# High_Voltage_Converter.net
KiCad netlist of a schematic drawn in Altium Designer
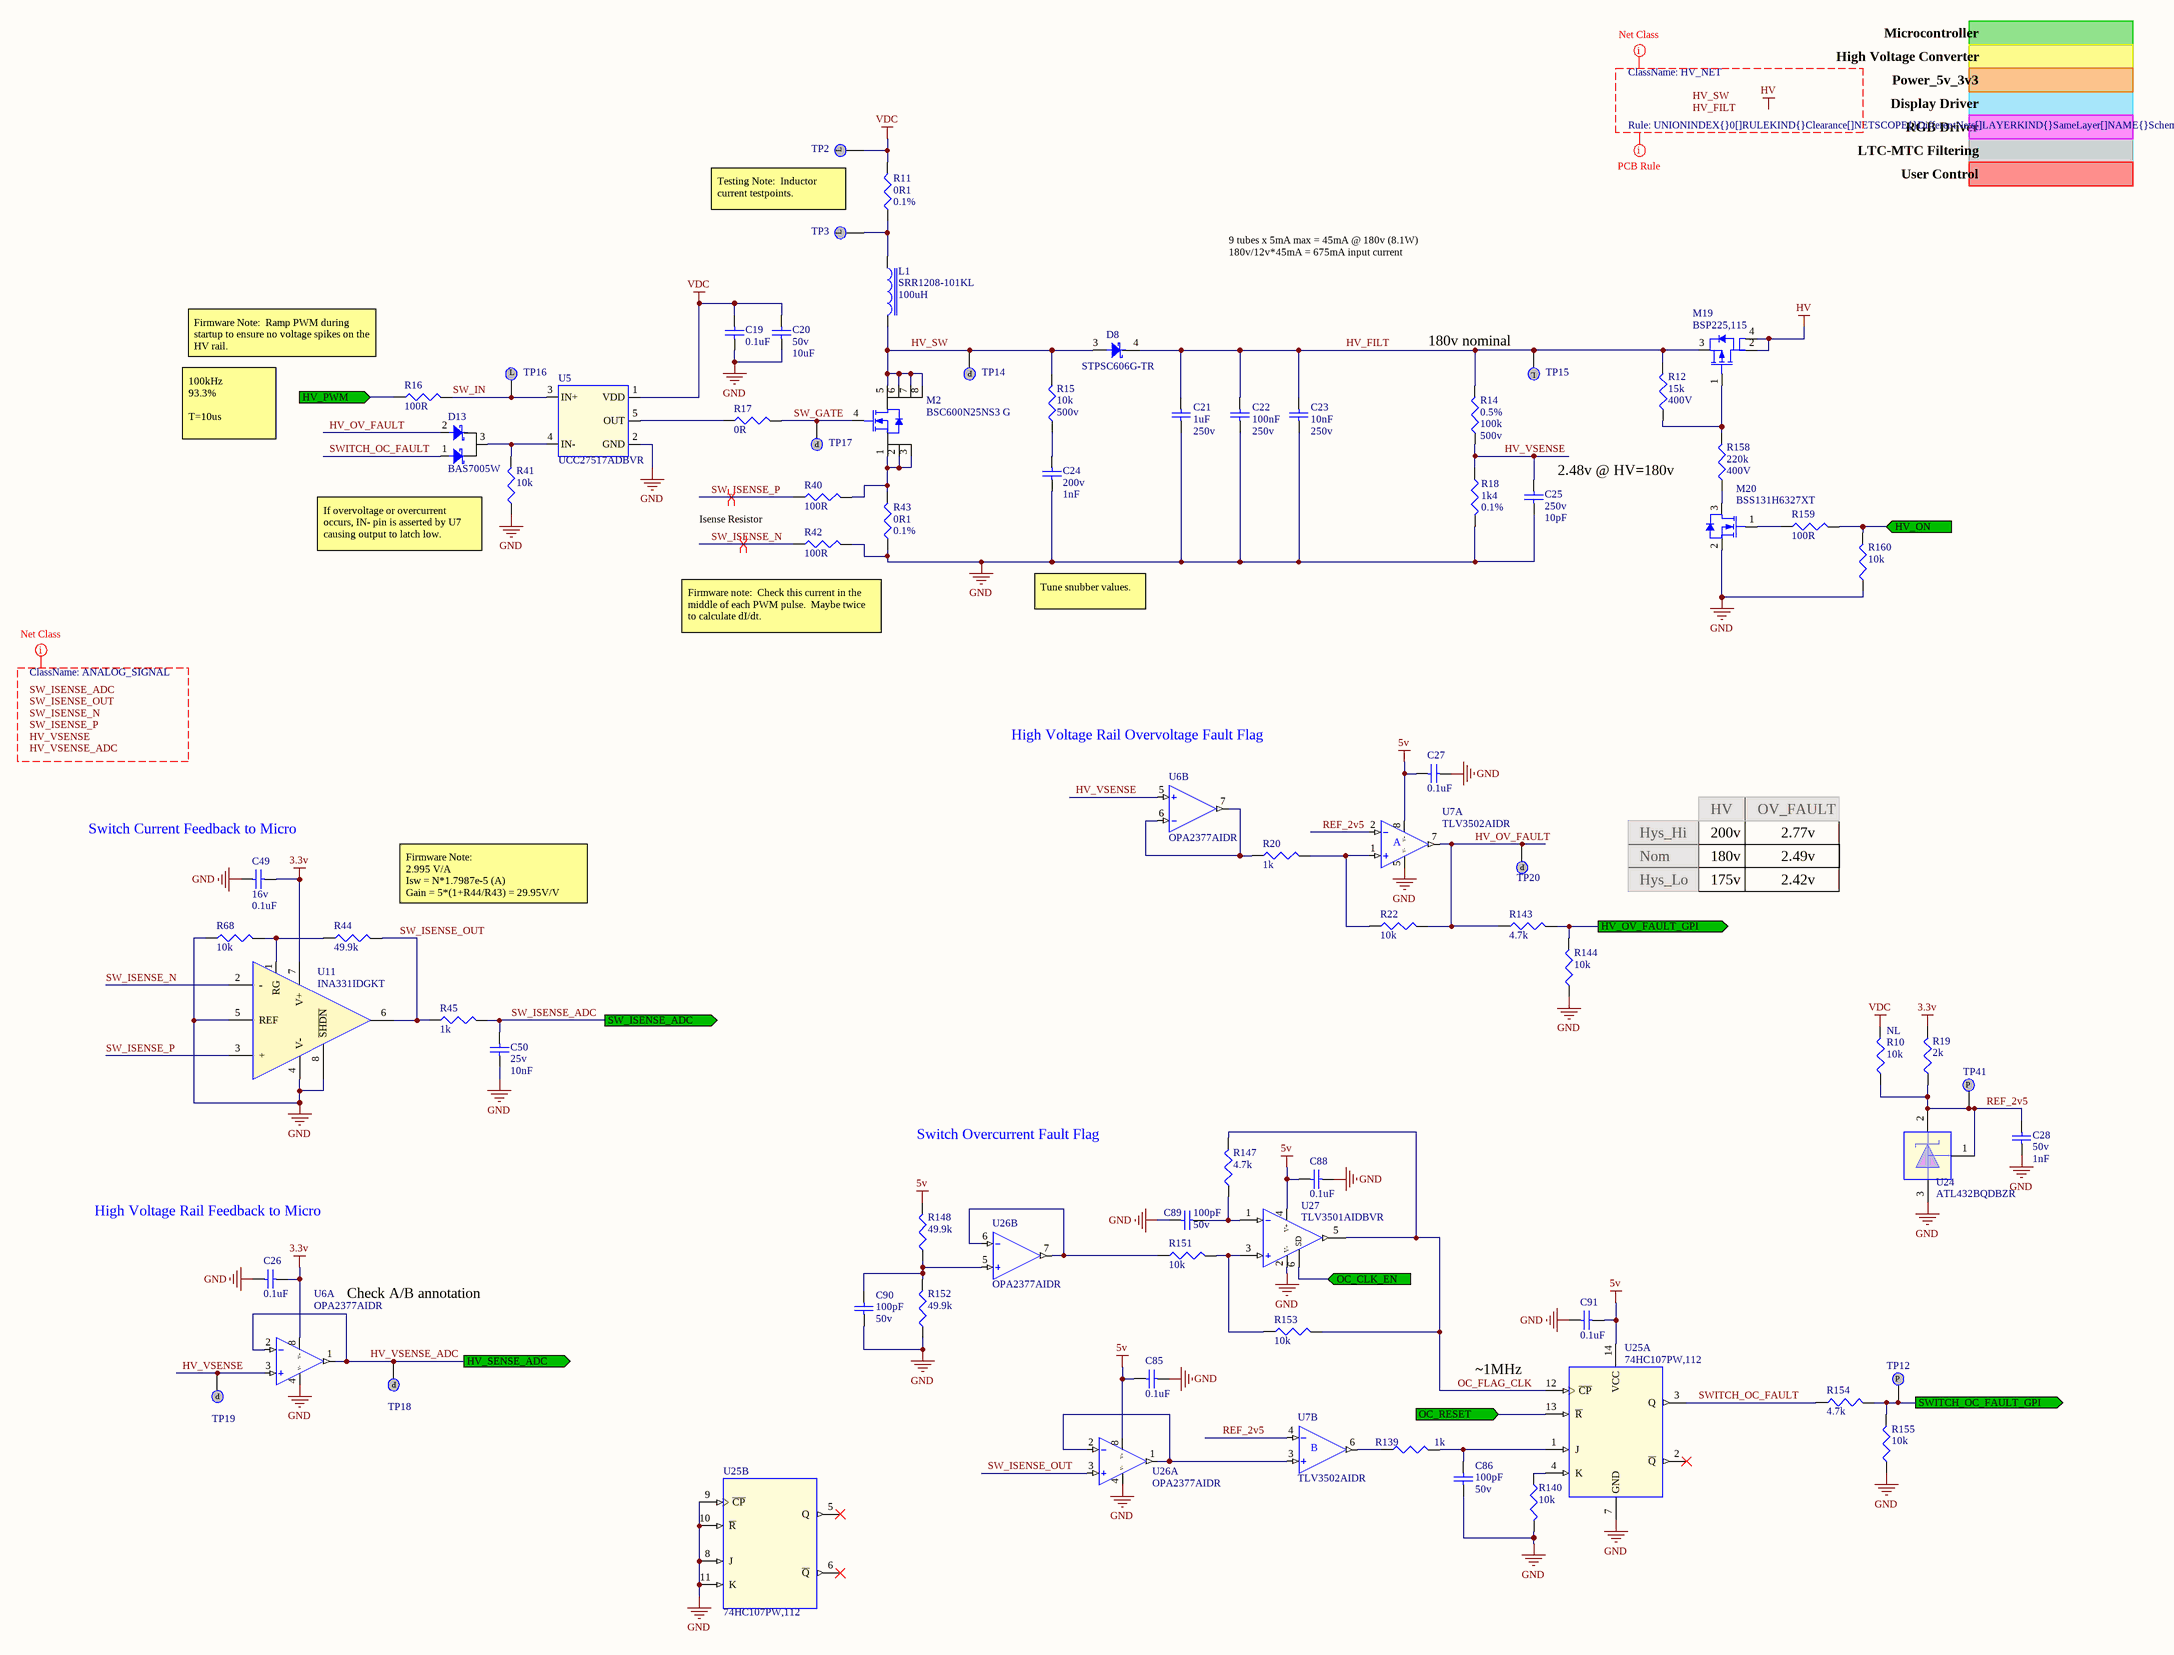
[diagram p0: High Voltage Converter.SchDoc]

(export (version "E")
  (design (tool "Eeschema 10.0.6"))
  (components
    (comp (ref "C19")
      (value "0.1uF")
      (footprint "CAP0603R")
      (fields (field (name "MFG") "Vishay") (field (name "VOLTAGE") "50v"))
      (libsource (lib "Altium Library") (part "0.1uF 50v (0603)"))
    )
    (comp (ref "C20")
      (value "10uF")
      (footprint "CAP1206R")
      (fields (field (name "TOLERANCE") "10%") (field (name "MFG") "TDK") (field (name "VOLTAGE") "50v"))
      (libsource (lib "Altium Library") (part "10uF 50v (1206)"))
    )
    (comp (ref "C21")
      (value "1uF")
      (footprint "CAP2220R")
      (fields (field (name "TOLERANCE") "10%") (field (name "MFG") "Murata") (field (name "VOLTAGE") "250v"))
      (libsource (lib "Altium Library") (part "1uF 250v (2220)"))
    )
    (comp (ref "C22")
      (value "100nF")
      (footprint "CAP1206R")
      (fields (field (name "TOLERANCE") "10%") (field (name "MFG") "Murata") (field (name "VOLTAGE") "250v"))
      (libsource (lib "Altium Library") (part "100nF 250v (1206)"))
    )
    (comp (ref "C23")
      (value "10nF")
      (footprint "CAP0805R")
      (fields (field (name "TOLERANCE") "10%") (field (name "MFG") "Murata") (field (name "VOLTAGE") "250v"))
      (libsource (lib "Altium Library") (part "10nF 250v (0805)"))
    )
    (comp (ref "C24")
      (value "1nF")
      (footprint "CAP0805R")
      (fields (field (name "MFG") "Vishay") (field (name "VOLTAGE") "200v"))
      (libsource (lib "Altium Library") (part "1nF 200v (0805)"))
    )
    (comp (ref "C25")
      (value "10pF")
      (footprint "CAP0805R")
      (fields (field (name "TOLERANCE") "5%") (field (name "MFG") "Murata") (field (name "VOLTAGE") "250v"))
      (libsource (lib "Altium Library") (part "10pF 250V (0805)"))
    )
    (comp (ref "C26")
      (value "0.1uF")
      (footprint "CAP0402R")
      (fields (field (name "TOLERANCE") "20%") (field (name "MFG") "Vishay") (field (name "VOLTAGE") "10v"))
      (libsource (lib "Altium Library") (part "0.1uF 10v (0402)"))
    )
    (comp (ref "C27")
      (value "0.1uF")
      (footprint "CAP0402R")
      (fields (field (name "TOLERANCE") "20%") (field (name "MFG") "Vishay") (field (name "VOLTAGE") "10v"))
      (libsource (lib "Altium Library") (part "0.1uF 10v (0402)"))
    )
    (comp (ref "C28")
      (value "1nF")
      (footprint "CAP0402R")
      (fields (field (name "TOLERANCE") "10%") (field (name "MFG") "Vishay") (field (name "VOLTAGE") "50v"))
      (libsource (lib "Altium Library") (part "1nF 50v (0402)"))
    )
    (comp (ref "C49")
      (value "0.1uF")
      (footprint "CAP0603R")
      (fields (field (name "MFG") "Vishay") (field (name "VOLTAGE") "16v"))
      (libsource (lib "Altium Library") (part "0.1uF 16v (0603)"))
    )
    (comp (ref "C50")
      (value "10nF")
      (footprint "CAP0402R")
      (fields (field (name "TOLERANCE") "5%") (field (name "MFG") "Vishay") (field (name "VOLTAGE") "25v"))
      (libsource (lib "Altium Library") (part "10nF 25v (0402)"))
    )
    (comp (ref "C85")
      (value "0.1uF")
      (footprint "CAP0402R")
      (fields (field (name "TOLERANCE") "20%") (field (name "MFG") "Vishay") (field (name "VOLTAGE") "10v"))
      (libsource (lib "Altium Library") (part "0.1uF 10v (0402)"))
    )
    (comp (ref "C86")
      (value "100pF")
      (footprint "CAP0402R")
      (fields (field (name "TOLERANCE") "10%") (field (name "MFG") "MURATA") (field (name "VOLTAGE") "50v"))
      (libsource (lib "Altium Library") (part "100pF 50v (0402)"))
    )
    (comp (ref "C88")
      (value "0.1uF")
      (footprint "CAP0402R")
      (fields (field (name "TOLERANCE") "20%") (field (name "MFG") "Vishay") (field (name "VOLTAGE") "10v"))
      (libsource (lib "Altium Library") (part "0.1uF 10v (0402)"))
    )
    (comp (ref "C89")
      (value "100pF")
      (footprint "CAP0402R")
      (fields (field (name "TOLERANCE") "10%") (field (name "MFG") "MURATA") (field (name "VOLTAGE") "50v"))
      (libsource (lib "Altium Library") (part "100pF 50v (0402)"))
    )
    (comp (ref "C90")
      (value "100pF")
      (footprint "CAP0402R")
      (fields (field (name "TOLERANCE") "10%") (field (name "MFG") "MURATA") (field (name "VOLTAGE") "50v"))
      (libsource (lib "Altium Library") (part "100pF 50v (0402)"))
    )
    (comp (ref "C91")
      (value "0.1uF")
      (footprint "CAP0402R")
      (fields (field (name "TOLERANCE") "20%") (field (name "MFG") "Vishay") (field (name "VOLTAGE") "10v"))
      (libsource (lib "Altium Library") (part "0.1uF 10v (0402)"))
    )
    (comp (ref "D8")
      (value "STPSC606G-TR")
      (footprint "D2PAK-3")
      (description "Schottky, 6A, 600v")
      (fields (field (name "MFG") "STMICRO"))
      (libsource (lib "Altium Library") (part "STPSC606G-TR"))
    )
    (comp (ref "D13")
      (value "BAS7005W")
      (footprint "SOT-323")
      (description "Schottky, Dual, Common Cathode")
      (fields (field (name "MFG") "Vishay"))
      (libsource (lib "Altium Library") (part "BAS7005WH6327XTSA1"))
    )
    (comp (ref "L1")
      (value "100uH")
      (footprint "SRR1208")
      (fields (field (name "MFG") "Bourns") (field (name "MFG_PN") "SRR1208-101KL"))
      (libsource (lib "Altium Library") (part "100uH_SRR1208"))
    )
    (comp (ref "M2")
      (value "BSC600N25NS3 G")
      (footprint "PowerPAK-SO8")
      (description "NFET_SINGLE_25A_250V")
      (fields (field (name "MFG") "Infineon") (field (name "MFG_PN") "BSC600N25NS3 G"))
      (libsource (lib "Altium Library") (part "BSC600N25NS3 G"))
    )
    (comp (ref "M19")
      (value "BSP225,115")
      (footprint "SOT223")
      (description "PFET_SINGLE_0.225A_1.5W_250V")
      (fields (field (name "MFG") "NXP"))
      (libsource (lib "Altium Library") (part "BSP225,115"))
    )
    (comp (ref "M20")
      (value "BSS131H6327XT")
      (footprint "SOT23-3 REFLOW")
      (description "NFET_SINGLE_100mA_240v")
      (fields (field (name "MFG") "INFINEON"))
      (libsource (lib "Altium Library") (part "BSS131H6327XT"))
    )
    (comp (ref "R10")
      (value "10k")
      (footprint "RES0402R")
      (fields
        (field (name "TOLERANCE") "1%")
        (field (name "POWER") "63mW")
        (field (name "MFG") "Vishay")
        (field (name "LOAD") "NL")
      )
      (libsource (lib "Altium Library") (part "10k (0402)"))
    )
    (comp (ref "R11")
      (value "0R1")
      (footprint "RES1206R")
      (fields (field (name "POWER") "1W") (field (name "MFG") "Vishay") (field (name "TOLERANCE") "0.1%"))
      (libsource (lib "Altium Library") (part "100m 0.1% (1206)"))
    )
    (comp (ref "R12")
      (value "15k")
      (footprint "RES2010R")
      (fields
        (field (name "TOLERANCE") "1%")
        (field (name "POWER") "0.750mW")
        (field (name "MFG") "VISHAY")
        (field (name "VOLTAGE") "400V")
      )
      (libsource (lib "Altium Library") (part "15k 400v (2010)"))
    )
    (comp (ref "R14")
      (value "100k")
      (footprint "RES1206R")
      (fields
        (field (name "POWER") "0.25mW")
        (field (name "MFG") "KOA SPEER")
        (field (name "TOLERANCE") "0.5%")
        (field (name "VOLTAGE") "500v")
      )
      (libsource (lib "Altium Library") (part "100k 500v (1206)"))
    )
    (comp (ref "R15")
      (value "10k")
      (footprint "RES1206R")
      (fields
        (field (name "TOLERANCE") "5%")
        (field (name "POWER") "0.66mW")
        (field (name "MFG") "Panasonic")
        (field (name "VOLTAGE") "500v")
      )
      (libsource (lib "Altium Library") (part "10k 500v (1206)"))
    )
    (comp (ref "R16")
      (value "100R")
      (footprint "RES0402R")
      (fields (field (name "TOLERANCE") "1%") (field (name "POWER") "63mW") (field (name "MFG") "Vishay"))
      (libsource (lib "Altium Library") (part "100R (0402)"))
    )
    (comp (ref "R17")
      (value "0R")
      (footprint "RES0603R")
      (fields (field (name "MFG") "Vishay"))
      (libsource (lib "Altium Library") (part "0R (0603)"))
    )
    (comp (ref "R18")
      (value "1k4")
      (footprint "RES0603R")
      (fields (field (name "TOLERANCE") "0.1%") (field (name "POWER") "0.1W"))
      (libsource (lib "Altium Library") (part "1k4   0.1%"))
    )
    (comp (ref "R19")
      (value "2k")
      (footprint "RES0402R")
      (fields (field (name "TOLERANCE") "1%") (field (name "POWER") "63mW") (field (name "MFG") "Vishay"))
      (libsource (lib "Altium Library") (part "2k (0402)"))
    )
    (comp (ref "R20")
      (value "1k")
      (footprint "RES0402R")
      (fields (field (name "TOLERANCE") "1%") (field (name "POWER") "63mW") (field (name "MFG") "Vishay"))
      (libsource (lib "Altium Library") (part "1k (0402)"))
    )
    (comp (ref "R22")
      (value "10k")
      (footprint "RES0402R")
      (fields (field (name "TOLERANCE") "1%") (field (name "POWER") "63mW") (field (name "MFG") "Vishay"))
      (libsource (lib "Altium Library") (part "10k (0402)"))
    )
    (comp (ref "R40")
      (value "100R")
      (footprint "RES0402R")
      (fields (field (name "TOLERANCE") "1%") (field (name "POWER") "63mW") (field (name "MFG") "Vishay"))
      (libsource (lib "Altium Library") (part "100R (0402)"))
    )
    (comp (ref "R41")
      (value "10k")
      (footprint "RES0402R")
      (fields (field (name "TOLERANCE") "1%") (field (name "POWER") "63mW") (field (name "MFG") "Vishay"))
      (libsource (lib "Altium Library") (part "10k (0402)"))
    )
    (comp (ref "R42")
      (value "100R")
      (footprint "RES0402R")
      (fields (field (name "TOLERANCE") "1%") (field (name "POWER") "63mW") (field (name "MFG") "Vishay"))
      (libsource (lib "Altium Library") (part "100R (0402)"))
    )
    (comp (ref "R43")
      (value "0R1")
      (footprint "RES1206R")
      (fields (field (name "POWER") "1W") (field (name "MFG") "Vishay") (field (name "TOLERANCE") "0.1%"))
      (libsource (lib "Altium Library") (part "100m 0.1% (1206)"))
    )
    (comp (ref "R44")
      (value "49.9k")
      (footprint "RES0402R")
      (fields (field (name "TOLERANCE") "1%") (field (name "POWER") "63mW") (field (name "MFG") "Vishay"))
      (libsource (lib "Altium Library") (part "49.9k (0402)"))
    )
    (comp (ref "R45")
      (value "1k")
      (footprint "RES0402R")
      (fields (field (name "TOLERANCE") "1%") (field (name "POWER") "63mW") (field (name "MFG") "Vishay"))
      (libsource (lib "Altium Library") (part "1k (0402)"))
    )
    (comp (ref "R68")
      (value "10k")
      (footprint "RES0402R")
      (fields (field (name "TOLERANCE") "1%") (field (name "POWER") "63mW") (field (name "MFG") "Vishay"))
      (libsource (lib "Altium Library") (part "10k (0402)"))
    )
    (comp (ref "R139")
      (value "1k")
      (footprint "RES0402R")
      (fields (field (name "TOLERANCE") "1%") (field (name "POWER") "63mW") (field (name "MFG") "Vishay"))
      (libsource (lib "Altium Library") (part "1k (0402)"))
    )
    (comp (ref "R140")
      (value "10k")
      (footprint "RES0402R")
      (fields (field (name "TOLERANCE") "1%") (field (name "POWER") "63mW") (field (name "MFG") "Vishay"))
      (libsource (lib "Altium Library") (part "10k (0402)"))
    )
    (comp (ref "R143")
      (value "4.7k")
      (footprint "RES0402R")
      (fields (field (name "TOLERANCE") "1%") (field (name "POWER") "63mW") (field (name "MFG") "Vishay"))
      (libsource (lib "Altium Library") (part "4.7k (0402)"))
    )
    (comp (ref "R144")
      (value "10k")
      (footprint "RES0402R")
      (fields (field (name "TOLERANCE") "1%") (field (name "POWER") "63mW") (field (name "MFG") "Vishay"))
      (libsource (lib "Altium Library") (part "10k (0402)"))
    )
    (comp (ref "R147")
      (value "4.7k")
      (footprint "RES0402R")
      (fields (field (name "TOLERANCE") "1%") (field (name "POWER") "63mW") (field (name "MFG") "Vishay"))
      (libsource (lib "Altium Library") (part "4.7k (0402)"))
    )
    (comp (ref "R148")
      (value "49.9k")
      (footprint "RES0402R")
      (fields (field (name "TOLERANCE") "1%") (field (name "POWER") "63mW") (field (name "MFG") "Vishay"))
      (libsource (lib "Altium Library") (part "49.9k (0402)"))
    )
    (comp (ref "R151")
      (value "10k")
      (footprint "RES0402R")
      (fields (field (name "TOLERANCE") "1%") (field (name "POWER") "63mW") (field (name "MFG") "Vishay"))
      (libsource (lib "Altium Library") (part "10k (0402)"))
    )
    (comp (ref "R152")
      (value "49.9k")
      (footprint "RES0402R")
      (fields (field (name "TOLERANCE") "1%") (field (name "POWER") "63mW") (field (name "MFG") "Vishay"))
      (libsource (lib "Altium Library") (part "49.9k (0402)"))
    )
    (comp (ref "R153")
      (value "10k")
      (footprint "RES0402R")
      (fields (field (name "TOLERANCE") "1%") (field (name "POWER") "63mW") (field (name "MFG") "Vishay"))
      (libsource (lib "Altium Library") (part "10k (0402)"))
    )
    (comp (ref "R154")
      (value "4.7k")
      (footprint "RES0402R")
      (fields (field (name "TOLERANCE") "1%") (field (name "POWER") "63mW") (field (name "MFG") "Vishay"))
      (libsource (lib "Altium Library") (part "4.7k (0402)"))
    )
    (comp (ref "R155")
      (value "10k")
      (footprint "RES0402R")
      (fields (field (name "TOLERANCE") "1%") (field (name "POWER") "63mW") (field (name "MFG") "Vishay"))
      (libsource (lib "Altium Library") (part "10k (0402)"))
    )
    (comp (ref "R158")
      (value "220k")
      (footprint "RES2010R")
      (fields
        (field (name "TOLERANCE") "1%")
        (field (name "POWER") "0.750mW")
        (field (name "MFG") "VISHAY")
        (field (name "VOLTAGE") "400V")
      )
      (libsource (lib "Altium Library") (part "220k 400v (2010)"))
    )
    (comp (ref "R159")
      (value "100R")
      (footprint "RES0402R")
      (fields (field (name "TOLERANCE") "1%") (field (name "POWER") "63mW") (field (name "MFG") "Vishay"))
      (libsource (lib "Altium Library") (part "100R (0402)"))
    )
    (comp (ref "R160")
      (value "10k")
      (footprint "RES0402R")
      (fields (field (name "TOLERANCE") "1%") (field (name "POWER") "63mW") (field (name "MFG") "Vishay"))
      (libsource (lib "Altium Library") (part "10k (0402)"))
    )
    (comp (ref "TP2")
      (value "5001")
      (footprint "5001 Testpoint")
      (fields (field (name "MFG") "KEYSTONE"))
      (libsource (lib "Altium Library") (part "Testpoint Loop"))
    )
    (comp (ref "TP3")
      (value "5001")
      (footprint "5001 Testpoint")
      (fields (field (name "MFG") "KEYSTONE"))
      (libsource (lib "Altium Library") (part "Testpoint Loop"))
    )
    (comp (ref "TP12")
      (value "NONE")
      (footprint "TESTPOINT - 1.5mm Round Pad")
      (description "1.5mm Testpoint")
      (libsource (lib "Altium Library") (part "Testpoint 1.5mm Pad"))
    )
    (comp (ref "TP14")
      (value "NONE")
      (footprint "TESTPOINT - 1.5mm Round Pad")
      (description "1.5mm Testpoint")
      (libsource (lib "Altium Library") (part "Testpoint 1.5mm Pad"))
    )
    (comp (ref "TP15")
      (value "5001")
      (footprint "5001 Testpoint")
      (fields (field (name "MFG") "KEYSTONE"))
      (libsource (lib "Altium Library") (part "Testpoint Loop"))
    )
    (comp (ref "TP16")
      (value "5001")
      (footprint "5001 Testpoint")
      (fields (field (name "MFG") "KEYSTONE"))
      (libsource (lib "Altium Library") (part "Testpoint Loop"))
    )
    (comp (ref "TP17")
      (value "NONE")
      (footprint "TESTPOINT - 1.5mm Round Pad")
      (description "1.5mm Testpoint")
      (libsource (lib "Altium Library") (part "Testpoint 1.5mm Pad"))
    )
    (comp (ref "TP18")
      (value "NONE")
      (footprint "TESTPOINT - 1.5mm Round Pad")
      (description "1.5mm Testpoint")
      (libsource (lib "Altium Library") (part "Testpoint 1.5mm Pad"))
    )
    (comp (ref "TP19")
      (value "NONE")
      (footprint "TESTPOINT - 1.5mm Round Pad")
      (description "1.5mm Testpoint")
      (libsource (lib "Altium Library") (part "Testpoint 1.5mm Pad"))
    )
    (comp (ref "TP20")
      (value "NONE")
      (footprint "TESTPOINT - 1.5mm Round Pad")
      (description "1.5mm Testpoint")
      (libsource (lib "Altium Library") (part "Testpoint 1.5mm Pad"))
    )
    (comp (ref "TP41")
      (value "NONE")
      (footprint "TESTPOINT - 1.5mm Round Pad")
      (description "1.5mm Testpoint")
      (libsource (lib "Altium Library") (part "Testpoint 1.5mm Pad"))
    )
    (comp (ref "U5")
      (value "UCC27517ADBVR")
      (footprint "SOT23-5")
      (description "Low Side Gate Driver")
      (fields (field (name "MFG") "TI"))
      (libsource (lib "Altium Library") (part "UCC27517ADBVR"))
    )
    (comp (ref "U6")
      (value "OPA2377AIDR")
      (footprint "SOIC-8")
      (description "OpAmp - 2 Channel")
      (fields (field (name "MFG") "TI"))
      (libsource (lib "Altium Library") (part "OPA2377AIDR"))
    )
    (comp (ref "U7")
      (value "TLV3502AIDR")
      (footprint "SOIC-8")
      (description "Comparator, Dual, High Speed")
      (fields (field (name "MFG") "TI"))
      (libsource (lib "Altium Library") (part "TLV3502AIDR"))
    )
    (comp (ref "U11")
      (value "INA331IDGKT")
      (footprint "VSSOP8")
      (description "Instrumentation Amplifier - 1 Channel")
      (fields (field (name "MFG") "TI"))
      (libsource (lib "Altium Library") (part "INA331IDGKT"))
    )
    (comp (ref "U24")
      (value "ATL432BQDBZR")
      (footprint "SOT23-3M")
      (description "Shunt Voltage Reference, 0.5%")
      (fields (field (name "MFG") "TI"))
      (libsource (lib "Altium Library") (part "ATL432BQDBZR"))
    )
    (comp (ref "U25")
      (value "74HC107PW,112")
      (footprint "TSSOP14")
      (description "Dual JK Flip Flop, Neg Edge Triggered")
      (fields (field (name "MFG") "NXP"))
      (libsource (lib "Altium Library") (part "74HC107D,653"))
    )
    (comp (ref "U26")
      (value "OPA2377AIDR")
      (footprint "SOIC-8")
      (description "OpAmp - 2 Channel")
      (fields (field (name "MFG") "TI"))
      (libsource (lib "Altium Library") (part "OPA2377AIDR"))
    )
    (comp (ref "U27")
      (value "TLV3501AIDBVR")
      (footprint "SOT23-6")
      (description "Comparator, Single, High Speed")
      (fields (field (name "MFG") "TI"))
      (libsource (lib "Altium Library") (part "TLV3501AIDBVR"))
    )
  )
  (nets
    (net (code "1") (name "/HV_FILT") (class "Default")
      (node (ref "C21") (pin "1") (pinfunction "1_1") (pintype "passive"))
      (node (ref "C22") (pin "1") (pinfunction "1_1") (pintype "passive"))
      (node (ref "C23") (pin "1") (pinfunction "1_1") (pintype "passive"))
      (node (ref "D8") (pin "4") (pinfunction "4_4") (pintype "passive"))
      (node (ref "M19") (pin "3") (pinfunction "SOURCE_3") (pintype "passive"))
      (node (ref "R12") (pin "2") (pinfunction "2_2") (pintype "passive"))
      (node (ref "R14") (pin "2") (pinfunction "2_2") (pintype "passive"))
      (node (ref "TP15") (pin "1") (pinfunction "1_1") (pintype "passive"))
    )
    (net (code "2") (name "/HV_ON") (class "Default")
      (node (ref "R159") (pin "2") (pinfunction "2_2") (pintype "passive"))
      (node (ref "R160") (pin "2") (pinfunction "2_2") (pintype "passive"))
    )
    (net (code "3") (name "/HV_OV_FAULT") (class "Default")
      (node (ref "D13") (pin "2") (pinfunction "A2_2") (pintype "passive"))
      (node (ref "R143") (pin "1") (pinfunction "1_1") (pintype "passive"))
      (node (ref "R22") (pin "2") (pinfunction "2_2") (pintype "passive"))
      (node (ref "TP20") (pin "1") (pinfunction "1_1") (pintype "passive"))
      (node (ref "U7") (pin "7") (pinfunction "OUT_A_7") (pintype "output"))
    )
    (net (code "4") (name "/HV_OV_FAULT_GPI") (class "Default")
      (node (ref "R143") (pin "2") (pinfunction "2_2") (pintype "passive"))
      (node (ref "R144") (pin "2") (pinfunction "2_2") (pintype "passive"))
    )
    (net (code "5") (name "/HV_PWM") (class "Default")
      (node (ref "R16") (pin "1") (pinfunction "1_1") (pintype "passive"))
    )
    (net (code "6") (name "/HV_SW") (class "Default")
      (node (ref "D8") (pin "3") (pinfunction "A_3") (pintype "passive"))
      (node (ref "L1") (pin "2") (pinfunction "2_2") (pintype "passive"))
      (node (ref "M2") (pin "5") (pinfunction "DRAIN_5") (pintype "passive"))
      (node (ref "M2") (pin "6") (pinfunction "DRAIN_6") (pintype "passive"))
      (node (ref "M2") (pin "7") (pinfunction "DRAIN_7") (pintype "passive"))
      (node (ref "M2") (pin "8") (pinfunction "DRAIN_8") (pintype "passive"))
      (node (ref "R15") (pin "2") (pinfunction "2_2") (pintype "passive"))
      (node (ref "TP14") (pin "1") (pinfunction "1_1") (pintype "passive"))
    )
    (net (code "7") (name "/HV_VSENSE") (class "Default")
      (node (ref "C25") (pin "1") (pinfunction "1_1") (pintype "passive"))
      (node (ref "R14") (pin "1") (pinfunction "1_1") (pintype "passive"))
      (node (ref "R18") (pin "1") (pinfunction "1_1") (pintype "passive"))
      (node (ref "TP19") (pin "1") (pinfunction "1_1") (pintype "passive"))
      (node (ref "U6") (pin "3") (pinfunction "+IN_A_3") (pintype "input"))
      (node (ref "U6") (pin "5") (pinfunction "+IN_B_5") (pintype "input"))
    )
    (net (code "8") (name "/HV_VSENSE_ADC") (class "Default")
      (node (ref "TP18") (pin "1") (pinfunction "1_1") (pintype "passive"))
      (node (ref "U6") (pin "1") (pinfunction "OUT_A_1") (pintype "output"))
      (node (ref "U6") (pin "2") (pinfunction "-IN_A_2") (pintype "input"))
    )
    (net (code "9") (name "/OC_CLK_EN") (class "Default")
      (node (ref "U27") (pin "6") (pinfunction "SD_6") (pintype "passive"))
    )
    (net (code "10") (name "/OC_FLAG_CLK") (class "Default")
      (node (ref "R147") (pin "2") (pinfunction "2_2") (pintype "passive"))
      (node (ref "R153") (pin "2") (pinfunction "2_2") (pintype "passive"))
      (node (ref "U25") (pin "12") (pinfunction "~{CP}_12") (pintype "input"))
      (node (ref "U27") (pin "5") (pinfunction "OUT_A_5") (pintype "output"))
    )
    (net (code "11") (name "/OC_RESET") (class "Default")
      (node (ref "U25") (pin "13") (pinfunction "~{R}_13") (pintype "input"))
    )
    (net (code "12") (name "/REF_2v5") (class "Default")
      (node (ref "C28") (pin "1") (pinfunction "1_1") (pintype "passive"))
      (node (ref "R10") (pin "1") (pinfunction "1_1") (pintype "passive"))
      (node (ref "R19") (pin "1") (pinfunction "1_1") (pintype "passive"))
      (node (ref "TP41") (pin "1") (pinfunction "1_1") (pintype "passive"))
      (node (ref "U24") (pin "1") (pinfunction "REF_1") (pintype "passive"))
      (node (ref "U24") (pin "2") (pinfunction "K_2") (pintype "passive"))
      (node (ref "U7") (pin "2") (pinfunction "-IN_A_2") (pintype "input"))
      (node (ref "U7") (pin "4") (pinfunction "-IN_A_4") (pintype "input"))
    )
    (net (code "13") (name "/SWITCH_OC_FAULT") (class "Default")
      (node (ref "D13") (pin "1") (pinfunction "A1_1") (pintype "passive"))
      (node (ref "R154") (pin "1") (pinfunction "1_1") (pintype "passive"))
      (node (ref "U25") (pin "3") (pinfunction "Q_3") (pintype "output"))
    )
    (net (code "14") (name "/SWITCH_OC_FAULT_GPI") (class "Default")
      (node (ref "R154") (pin "2") (pinfunction "2_2") (pintype "passive"))
      (node (ref "R155") (pin "2") (pinfunction "2_2") (pintype "passive"))
      (node (ref "TP12") (pin "1") (pinfunction "1_1") (pintype "passive"))
    )
    (net (code "15") (name "/SW_GATE") (class "Default")
      (node (ref "M2") (pin "4") (pinfunction "GATE_4") (pintype "passive"))
      (node (ref "R17") (pin "2") (pinfunction "2_2") (pintype "passive"))
      (node (ref "TP17") (pin "1") (pinfunction "1_1") (pintype "passive"))
    )
    (net (code "16") (name "/SW_IN") (class "Default")
      (node (ref "R16") (pin "2") (pinfunction "2_2") (pintype "passive"))
      (node (ref "TP16") (pin "1") (pinfunction "1_1") (pintype "passive"))
      (node (ref "U5") (pin "3") (pinfunction "IN+_3") (pintype "passive"))
    )
    (net (code "17") (name "/SW_ISENSE_ADC") (class "Default")
      (node (ref "C50") (pin "1") (pinfunction "1_1") (pintype "passive"))
      (node (ref "R45") (pin "2") (pinfunction "2_2") (pintype "passive"))
    )
    (net (code "18") (name "/SW_ISENSE_N") (class "Default")
      (node (ref "R42") (pin "1") (pinfunction "1_1") (pintype "passive"))
      (node (ref "U11") (pin "2") (pinfunction "-_2") (pintype "passive"))
    )
    (net (code "19") (name "/SW_ISENSE_OUT") (class "Default")
      (node (ref "R44") (pin "2") (pinfunction "2_2") (pintype "passive"))
      (node (ref "R45") (pin "1") (pinfunction "1_1") (pintype "passive"))
      (node (ref "U11") (pin "6") (pinfunction "OUT_6") (pintype "passive"))
      (node (ref "U26") (pin "3") (pinfunction "+IN_A_3") (pintype "input"))
    )
    (net (code "20") (name "/SW_ISENSE_P") (class "Default")
      (node (ref "R40") (pin "1") (pinfunction "1_1") (pintype "passive"))
      (node (ref "U11") (pin "3") (pinfunction "+_3") (pintype "passive"))
    )
    (net (code "21") (name "3.3v") (class "Default")
      (node (ref "C26") (pin "2") (pinfunction "2_2") (pintype "passive"))
      (node (ref "C49") (pin "2") (pinfunction "2_2") (pintype "passive"))
      (node (ref "R19") (pin "2") (pinfunction "2_2") (pintype "passive"))
      (node (ref "U11") (pin "7") (pinfunction "V+_7") (pintype "passive"))
      (node (ref "U6") (pin "8") (pinfunction "V+_8") (pintype "power_in"))
    )
    (net (code "22") (name "5v") (class "Default")
      (node (ref "C27") (pin "2") (pinfunction "2_2") (pintype "passive"))
      (node (ref "C85") (pin "2") (pinfunction "2_2") (pintype "passive"))
      (node (ref "C88") (pin "2") (pinfunction "2_2") (pintype "passive"))
      (node (ref "C91") (pin "2") (pinfunction "2_2") (pintype "passive"))
      (node (ref "R148") (pin "2") (pinfunction "2_2") (pintype "passive"))
      (node (ref "U25") (pin "14") (pinfunction "VCC_14") (pintype "power_in"))
      (node (ref "U26") (pin "8") (pinfunction "V+_8") (pintype "power_in"))
      (node (ref "U27") (pin "4") (pinfunction "V+_4") (pintype "power_in"))
      (node (ref "U7") (pin "8") (pinfunction "V+_8") (pintype "power_in"))
    )
    (net (code "23") (name "GND") (class "Default")
      (node (ref "C19") (pin "2") (pinfunction "2_2") (pintype "passive"))
      (node (ref "C20") (pin "1") (pinfunction "1_1") (pintype "passive"))
      (node (ref "C21") (pin "2") (pinfunction "2_2") (pintype "passive"))
      (node (ref "C22") (pin "2") (pinfunction "2_2") (pintype "passive"))
      (node (ref "C23") (pin "2") (pinfunction "2_2") (pintype "passive"))
      (node (ref "C24") (pin "2") (pinfunction "2_2") (pintype "passive"))
      (node (ref "C25") (pin "2") (pinfunction "2_2") (pintype "passive"))
      (node (ref "C26") (pin "1") (pinfunction "1_1") (pintype "passive"))
      (node (ref "C27") (pin "1") (pinfunction "1_1") (pintype "passive"))
      (node (ref "C28") (pin "2") (pinfunction "2_2") (pintype "passive"))
      (node (ref "C49") (pin "1") (pinfunction "1_1") (pintype "passive"))
      (node (ref "C50") (pin "2") (pinfunction "2_2") (pintype "passive"))
      (node (ref "C85") (pin "1") (pinfunction "1_1") (pintype "passive"))
      (node (ref "C86") (pin "2") (pinfunction "2_2") (pintype "passive"))
      (node (ref "C88") (pin "1") (pinfunction "1_1") (pintype "passive"))
      (node (ref "C89") (pin "1") (pinfunction "1_1") (pintype "passive"))
      (node (ref "C90") (pin "2") (pinfunction "2_2") (pintype "passive"))
      (node (ref "C91") (pin "1") (pinfunction "1_1") (pintype "passive"))
      (node (ref "M20") (pin "2") (pinfunction "SOURCE_2") (pintype "passive"))
      (node (ref "R140") (pin "2") (pinfunction "2_2") (pintype "passive"))
      (node (ref "R144") (pin "1") (pinfunction "1_1") (pintype "passive"))
      (node (ref "R152") (pin "1") (pinfunction "1_1") (pintype "passive"))
      (node (ref "R155") (pin "1") (pinfunction "1_1") (pintype "passive"))
      (node (ref "R160") (pin "1") (pinfunction "1_1") (pintype "passive"))
      (node (ref "R18") (pin "2") (pinfunction "2_2") (pintype "passive"))
      (node (ref "R41") (pin "1") (pinfunction "1_1") (pintype "passive"))
      (node (ref "R42") (pin "2") (pinfunction "2_2") (pintype "passive"))
      (node (ref "R43") (pin "1") (pinfunction "1_1") (pintype "passive"))
      (node (ref "R68") (pin "1") (pinfunction "1_1") (pintype "passive"))
      (node (ref "U11") (pin "4") (pinfunction "V-_4") (pintype "passive"))
      (node (ref "U11") (pin "5") (pinfunction "REF_5") (pintype "passive"))
      (node (ref "U11") (pin "8") (pinfunction "~{SHDN}_8") (pintype "passive"))
      (node (ref "U24") (pin "3") (pinfunction "A_3") (pintype "passive"))
      (node (ref "U25") (pin "10") (pinfunction "~{R}_10") (pintype "input"))
      (node (ref "U25") (pin "11") (pinfunction "K_11") (pintype "input"))
      (node (ref "U25") (pin "7") (pinfunction "GND_7") (pintype "power_in"))
      (node (ref "U25") (pin "8") (pinfunction "J_8") (pintype "input"))
      (node (ref "U25") (pin "9") (pinfunction "~{CP}_9") (pintype "input"))
      (node (ref "U26") (pin "4") (pinfunction "V-_4") (pintype "power_in"))
      (node (ref "U27") (pin "2") (pinfunction "V-_2") (pintype "power_in"))
      (node (ref "U5") (pin "2") (pinfunction "GND_2") (pintype "passive"))
      (node (ref "U6") (pin "4") (pinfunction "V-_4") (pintype "power_in"))
      (node (ref "U7") (pin "5") (pinfunction "V-_5") (pintype "power_in"))
    )
    (net (code "24") (name "HV") (class "Default")
      (node (ref "M19") (pin "2") (pinfunction "DRAIN_2") (pintype "passive"))
      (node (ref "M19") (pin "4") (pinfunction "DRAIN_4") (pintype "passive"))
    )
    (net (code "25") (name "Net-(C24-Pad1)") (class "Default")
      (node (ref "C24") (pin "1") (pinfunction "1_1") (pintype "passive"))
      (node (ref "R15") (pin "1") (pinfunction "1_1") (pintype "passive"))
    )
    (net (code "26") (name "Net-(D13-C)") (class "Default")
      (node (ref "D13") (pin "3") (pinfunction "C_3") (pintype "passive"))
      (node (ref "R41") (pin "2") (pinfunction "2_2") (pintype "passive"))
      (node (ref "U5") (pin "4") (pinfunction "IN-_4") (pintype "passive"))
    )
    (net (code "27") (name "Net-(L1-Pad1)") (class "Default")
      (node (ref "L1") (pin "1") (pinfunction "1_1") (pintype "passive"))
      (node (ref "R11") (pin "1") (pinfunction "1_1") (pintype "passive"))
      (node (ref "TP3") (pin "1") (pinfunction "1_1") (pintype "passive"))
    )
    (net (code "28") (name "Net-(M2-SOURCE-Pad1)") (class "Default")
      (node (ref "M2") (pin "1") (pinfunction "SOURCE_1") (pintype "passive"))
      (node (ref "M2") (pin "2") (pinfunction "SOURCE_2") (pintype "passive"))
      (node (ref "M2") (pin "3") (pinfunction "SOURCE_3") (pintype "passive"))
      (node (ref "R40") (pin "2") (pinfunction "2_2") (pintype "passive"))
      (node (ref "R43") (pin "2") (pinfunction "2_2") (pintype "passive"))
    )
    (net (code "29") (name "Net-(M19-GATE)") (class "Default")
      (node (ref "M19") (pin "1") (pinfunction "GATE_1") (pintype "passive"))
      (node (ref "R12") (pin "1") (pinfunction "1_1") (pintype "passive"))
      (node (ref "R158") (pin "2") (pinfunction "2_2") (pintype "passive"))
    )
    (net (code "30") (name "Net-(M20-DRAIN)") (class "Default")
      (node (ref "M20") (pin "3") (pinfunction "DRAIN_3") (pintype "passive"))
      (node (ref "R158") (pin "1") (pinfunction "1_1") (pintype "passive"))
    )
    (net (code "31") (name "Net-(M20-GATE)") (class "Default")
      (node (ref "M20") (pin "1") (pinfunction "GATE_1") (pintype "passive"))
      (node (ref "R159") (pin "1") (pinfunction "1_1") (pintype "passive"))
    )
    (net (code "32") (name "Net-(U5-OUT)") (class "Default")
      (node (ref "R17") (pin "1") (pinfunction "1_1") (pintype "passive"))
      (node (ref "U5") (pin "5") (pinfunction "OUT_5") (pintype "passive"))
    )
    (net (code "33") (name "Net-(U6B--IN_B)") (class "Default")
      (node (ref "R20") (pin "1") (pinfunction "1_1") (pintype "passive"))
      (node (ref "U6") (pin "6") (pinfunction "-IN_B_6") (pintype "input"))
      (node (ref "U6") (pin "7") (pinfunction "OUT_B_7") (pintype "output"))
    )
    (net (code "34") (name "Net-(U7A-+IN_A)") (class "Default")
      (node (ref "R20") (pin "2") (pinfunction "2_2") (pintype "passive"))
      (node (ref "R22") (pin "1") (pinfunction "1_1") (pintype "passive"))
      (node (ref "U7") (pin "1") (pinfunction "+IN_A_1") (pintype "input"))
    )
    (net (code "35") (name "Net-(U7B-OUT_A)") (class "Default")
      (node (ref "R139") (pin "1") (pinfunction "1_1") (pintype "passive"))
      (node (ref "U7") (pin "6") (pinfunction "OUT_A_6") (pintype "output"))
    )
    (net (code "36") (name "Net-(U11-RG)") (class "Default")
      (node (ref "R44") (pin "1") (pinfunction "1_1") (pintype "passive"))
      (node (ref "R68") (pin "2") (pinfunction "2_2") (pintype "passive"))
      (node (ref "U11") (pin "1") (pinfunction "RG_1") (pintype "passive"))
    )
    (net (code "37") (name "Net-(U25A-J)") (class "Default")
      (node (ref "C86") (pin "1") (pinfunction "1_1") (pintype "passive"))
      (node (ref "R139") (pin "2") (pinfunction "2_2") (pintype "passive"))
      (node (ref "U25") (pin "1") (pinfunction "J_1") (pintype "input"))
    )
    (net (code "38") (name "Net-(U25A-K)") (class "Default")
      (node (ref "R140") (pin "1") (pinfunction "1_1") (pintype "passive"))
      (node (ref "U25") (pin "4") (pinfunction "K_4") (pintype "input"))
    )
    (net (code "39") (name "Net-(U26A--IN_A)") (class "Default")
      (node (ref "U26") (pin "1") (pinfunction "OUT_A_1") (pintype "output"))
      (node (ref "U26") (pin "2") (pinfunction "-IN_A_2") (pintype "input"))
      (node (ref "U7") (pin "3") (pinfunction "+IN_A_3") (pintype "input"))
    )
    (net (code "40") (name "Net-(U26B-+IN_B)") (class "Default")
      (node (ref "C90") (pin "1") (pinfunction "1_1") (pintype "passive"))
      (node (ref "R148") (pin "1") (pinfunction "1_1") (pintype "passive"))
      (node (ref "R152") (pin "2") (pinfunction "2_2") (pintype "passive"))
      (node (ref "U26") (pin "5") (pinfunction "+IN_B_5") (pintype "input"))
    )
    (net (code "41") (name "Net-(U26B--IN_B)") (class "Default")
      (node (ref "R151") (pin "1") (pinfunction "1_1") (pintype "passive"))
      (node (ref "U26") (pin "6") (pinfunction "-IN_B_6") (pintype "input"))
      (node (ref "U26") (pin "7") (pinfunction "OUT_B_7") (pintype "output"))
    )
    (net (code "42") (name "Net-(U27-+IN_A)") (class "Default")
      (node (ref "R151") (pin "2") (pinfunction "2_2") (pintype "passive"))
      (node (ref "R153") (pin "1") (pinfunction "1_1") (pintype "passive"))
      (node (ref "U27") (pin "3") (pinfunction "+IN_A_3") (pintype "input"))
    )
    (net (code "43") (name "Net-(U27--IN_A)") (class "Default")
      (node (ref "C89") (pin "2") (pinfunction "2_2") (pintype "passive"))
      (node (ref "R147") (pin "1") (pinfunction "1_1") (pintype "passive"))
      (node (ref "U27") (pin "1") (pinfunction "-IN_A_1") (pintype "input"))
    )
    (net (code "44") (name "VDC") (class "Default")
      (node (ref "C19") (pin "1") (pinfunction "1_1") (pintype "passive"))
      (node (ref "C20") (pin "2") (pinfunction "2_2") (pintype "passive"))
      (node (ref "R10") (pin "2") (pinfunction "2_2") (pintype "passive"))
      (node (ref "R11") (pin "2") (pinfunction "2_2") (pintype "passive"))
      (node (ref "TP2") (pin "1") (pinfunction "1_1") (pintype "passive"))
      (node (ref "U5") (pin "1") (pinfunction "VDD_1") (pintype "passive"))
    )
    (net (code "45") (name "unconnected-(U25A-~{Q}-Pad2)") (class "Default")
      (node (ref "U25") (pin "2") (pinfunction "~{Q}_2") (pintype "output+no_connect"))
    )
    (net (code "46") (name "unconnected-(U25B-Q-Pad5)") (class "Default")
      (node (ref "U25") (pin "5") (pinfunction "Q_5") (pintype "output+no_connect"))
    )
    (net (code "47") (name "unconnected-(U25B-~{Q}-Pad6)") (class "Default")
      (node (ref "U25") (pin "6") (pinfunction "~{Q}_6") (pintype "output+no_connect"))
    )
  )
)
